# Adafruit_HT16K33_breakout.net
KiCad netlist of a schematic drawn in EAGLE
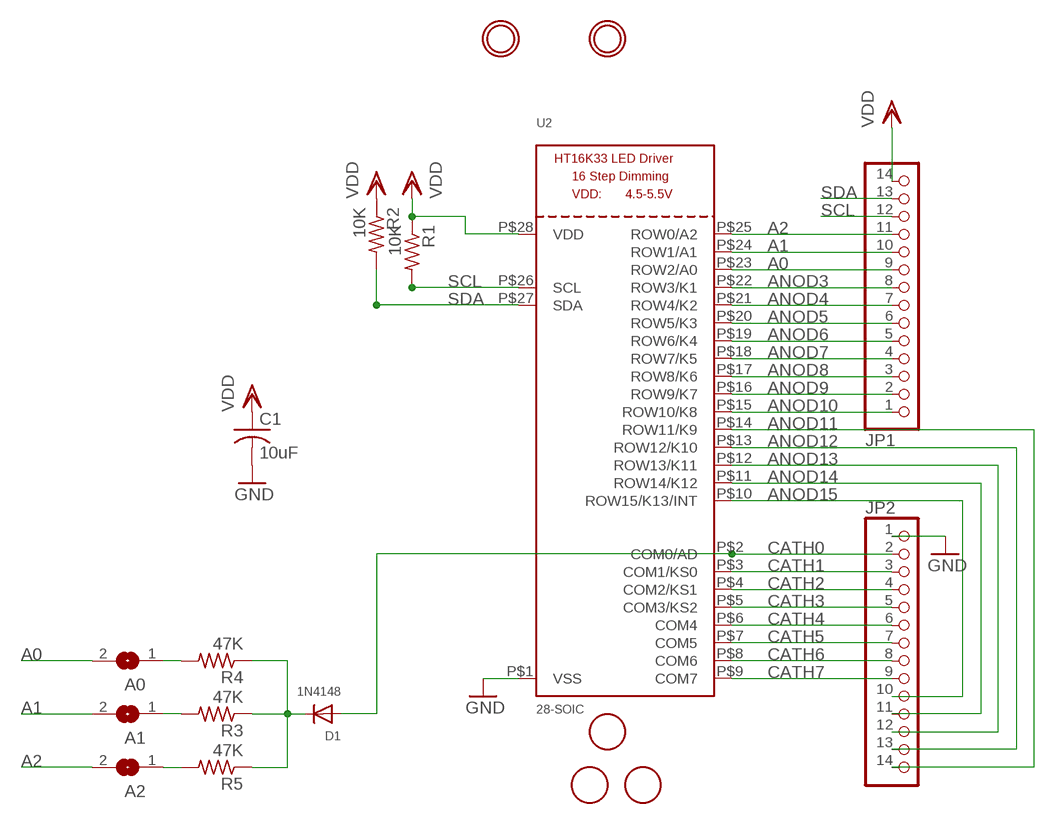
[diagram p0: schematic, sheet 1]

(export (version "E")
  (design (tool "Eeschema 10.0.6"))
  (components
    (comp (ref "A0")
      (value "SOLDERJUMPERREFLOW_NOPASTE")
      (footprint "eagle-import:SOLDERJUMPER_REFLOW_NOPASTE")
      (libsource (lib "eagle-import") (part "SOLDERJUMPERREFLOW_NOPASTE"))
    )
    (comp (ref "A1")
      (value "SOLDERJUMPERREFLOW_NOPASTE")
      (footprint "eagle-import:SOLDERJUMPER_REFLOW_NOPASTE")
      (libsource (lib "eagle-import") (part "SOLDERJUMPERREFLOW_NOPASTE"))
    )
    (comp (ref "A2")
      (value "SOLDERJUMPERREFLOW_NOPASTE")
      (footprint "eagle-import:SOLDERJUMPER_REFLOW_NOPASTE")
      (libsource (lib "eagle-import") (part "SOLDERJUMPERREFLOW_NOPASTE"))
    )
    (comp (ref "C1")
      (value "10uF")
      (footprint "eagle-import:C0805")
      (libsource (lib "eagle-import") (part "C-USC0805"))
    )
    (comp (ref "D1")
      (value "1N4148")
      (footprint "eagle-import:SOD-323F")
      (libsource (lib "eagle-import") (part "DIODESOD-323F"))
    )
    (comp (ref "JP1")
      (value "PINHD-1X14-CB")
      (footprint "eagle-import:1X14-CB")
      (libsource (lib "eagle-import") (part "PINHD-1X14-CB"))
    )
    (comp (ref "JP2")
      (value "PINHD-1X14-CB")
      (footprint "eagle-import:1X14-CB")
      (libsource (lib "eagle-import") (part "PINHD-1X14-CB"))
    )
    (comp (ref "R1")
      (value "10K")
      (footprint "eagle-import:R0805")
      (libsource (lib "eagle-import") (part "R-US_R0805"))
    )
    (comp (ref "R2")
      (value "10K")
      (footprint "eagle-import:R0805")
      (libsource (lib "eagle-import") (part "R-US_R0805"))
    )
    (comp (ref "R3")
      (value "47K")
      (footprint "eagle-import:R0805")
      (libsource (lib "eagle-import") (part "R-US_R0805"))
    )
    (comp (ref "R4")
      (value "47K")
      (footprint "eagle-import:R0805")
      (libsource (lib "eagle-import") (part "R-US_R0805"))
    )
    (comp (ref "R5")
      (value "47K")
      (footprint "eagle-import:R0805")
      (libsource (lib "eagle-import") (part "R-US_R0805"))
    )
    (comp (ref "U$1")
      (value "FIDUCIAL")
      (footprint "eagle-import:FIDUCIAL_1MM")
      (libsource (lib "eagle-import") (part "FIDUCIAL"))
    )
    (comp (ref "U$2")
      (value "FIDUCIAL")
      (footprint "eagle-import:FIDUCIAL_1MM")
      (libsource (lib "eagle-import") (part "FIDUCIAL"))
    )
    (comp (ref "U$4")
      (value "MOUNTINGHOLE2.5")
      (footprint "eagle-import:MOUNTINGHOLE_2.5_PLATED")
      (libsource (lib "eagle-import") (part "MOUNTINGHOLE2.5"))
    )
    (comp (ref "U$5")
      (value "MOUNTINGHOLE2.5")
      (footprint "eagle-import:MOUNTINGHOLE_2.5_PLATED")
      (libsource (lib "eagle-import") (part "MOUNTINGHOLE2.5"))
    )
    (comp (ref "U$6")
      (value "FIDUCIAL")
      (footprint "eagle-import:FIDUCIAL_1MM")
      (libsource (lib "eagle-import") (part "FIDUCIAL"))
    )
    (comp (ref "U2")
      (value "28-SOIC")
      (footprint "eagle-import:SOP28_300MIL")
      (libsource (lib "eagle-import") (part "HT16K33_SOP28"))
    )
  )
  (nets
    (net (code "1") (name "/A0") (class "Default")
      (node (ref "A0") (pin "2") (pinfunction "2_2") (pintype "passive"))
      (node (ref "JP1") (pin "9") (pinfunction "9_9") (pintype "passive"))
      (node (ref "U2") (pin "P$23") (pinfunction "ROW2/A0_P$23") (pintype "bidirectional"))
    )
    (net (code "2") (name "/A1") (class "Default")
      (node (ref "A1") (pin "2") (pinfunction "2_2") (pintype "passive"))
      (node (ref "JP1") (pin "10") (pinfunction "10_10") (pintype "passive"))
      (node (ref "U2") (pin "P$24") (pinfunction "ROW1/A1_P$24") (pintype "bidirectional"))
    )
    (net (code "3") (name "/A2") (class "Default")
      (node (ref "A2") (pin "2") (pinfunction "2_2") (pintype "passive"))
      (node (ref "JP1") (pin "11") (pinfunction "11_11") (pintype "passive"))
      (node (ref "U2") (pin "P$25") (pinfunction "ROW0/A2_P$25") (pintype "bidirectional"))
    )
    (net (code "4") (name "/ANOD3") (class "Default")
      (node (ref "JP1") (pin "8") (pinfunction "8_8") (pintype "passive"))
      (node (ref "U2") (pin "P$22") (pinfunction "ROW3/K1_P$22") (pintype "bidirectional"))
    )
    (net (code "5") (name "/ANOD4") (class "Default")
      (node (ref "JP1") (pin "7") (pinfunction "7_7") (pintype "passive"))
      (node (ref "U2") (pin "P$21") (pinfunction "ROW4/K2_P$21") (pintype "bidirectional"))
    )
    (net (code "6") (name "/ANOD5") (class "Default")
      (node (ref "JP1") (pin "6") (pinfunction "6_6") (pintype "passive"))
      (node (ref "U2") (pin "P$20") (pinfunction "ROW5/K3_P$20") (pintype "bidirectional"))
    )
    (net (code "7") (name "/ANOD6") (class "Default")
      (node (ref "JP1") (pin "5") (pinfunction "5_5") (pintype "passive"))
      (node (ref "U2") (pin "P$19") (pinfunction "ROW6/K4_P$19") (pintype "bidirectional"))
    )
    (net (code "8") (name "/ANOD7") (class "Default")
      (node (ref "JP1") (pin "4") (pinfunction "4_4") (pintype "passive"))
      (node (ref "U2") (pin "P$18") (pinfunction "ROW7/K5_P$18") (pintype "bidirectional"))
    )
    (net (code "9") (name "/ANOD8") (class "Default")
      (node (ref "JP1") (pin "3") (pinfunction "3_3") (pintype "passive"))
      (node (ref "U2") (pin "P$17") (pinfunction "ROW8/K6_P$17") (pintype "bidirectional"))
    )
    (net (code "10") (name "/ANOD9") (class "Default")
      (node (ref "JP1") (pin "2") (pinfunction "2_2") (pintype "passive"))
      (node (ref "U2") (pin "P$16") (pinfunction "ROW9/K7_P$16") (pintype "bidirectional"))
    )
    (net (code "11") (name "/ANOD10") (class "Default")
      (node (ref "JP1") (pin "1") (pinfunction "1_1") (pintype "passive"))
      (node (ref "U2") (pin "P$15") (pinfunction "ROW10/K8_P$15") (pintype "bidirectional"))
    )
    (net (code "12") (name "/ANOD11") (class "Default")
      (node (ref "JP2") (pin "14") (pinfunction "14_14") (pintype "passive"))
      (node (ref "U2") (pin "P$14") (pinfunction "ROW11/K9_P$14") (pintype "bidirectional"))
    )
    (net (code "13") (name "/ANOD12") (class "Default")
      (node (ref "JP2") (pin "13") (pinfunction "13_13") (pintype "passive"))
      (node (ref "U2") (pin "P$13") (pinfunction "ROW12/K10_P$13") (pintype "bidirectional"))
    )
    (net (code "14") (name "/ANOD13") (class "Default")
      (node (ref "JP2") (pin "12") (pinfunction "12_12") (pintype "passive"))
      (node (ref "U2") (pin "P$12") (pinfunction "ROW13/K11_P$12") (pintype "bidirectional"))
    )
    (net (code "15") (name "/ANOD14") (class "Default")
      (node (ref "JP2") (pin "11") (pinfunction "11_11") (pintype "passive"))
      (node (ref "U2") (pin "P$11") (pinfunction "ROW14/K12_P$11") (pintype "bidirectional"))
    )
    (net (code "16") (name "/ANOD15") (class "Default")
      (node (ref "JP2") (pin "10") (pinfunction "10_10") (pintype "passive"))
      (node (ref "U2") (pin "P$10") (pinfunction "ROW15/K13/INT_P$10") (pintype "bidirectional"))
    )
    (net (code "17") (name "/CATH0") (class "Default")
      (node (ref "D1") (pin "A") (pinfunction "A_A") (pintype "passive"))
      (node (ref "JP2") (pin "2") (pinfunction "2_2") (pintype "passive"))
      (node (ref "U2") (pin "P$2") (pinfunction "COM0/AD_P$2") (pintype "bidirectional"))
    )
    (net (code "18") (name "/CATH1") (class "Default")
      (node (ref "JP2") (pin "3") (pinfunction "3_3") (pintype "passive"))
      (node (ref "U2") (pin "P$3") (pinfunction "COM1/KS0_P$3") (pintype "bidirectional"))
    )
    (net (code "19") (name "/CATH2") (class "Default")
      (node (ref "JP2") (pin "4") (pinfunction "4_4") (pintype "passive"))
      (node (ref "U2") (pin "P$4") (pinfunction "COM2/KS1_P$4") (pintype "bidirectional"))
    )
    (net (code "20") (name "/CATH3") (class "Default")
      (node (ref "JP2") (pin "5") (pinfunction "5_5") (pintype "passive"))
      (node (ref "U2") (pin "P$5") (pinfunction "COM3/KS2_P$5") (pintype "bidirectional"))
    )
    (net (code "21") (name "/CATH4") (class "Default")
      (node (ref "JP2") (pin "6") (pinfunction "6_6") (pintype "passive"))
      (node (ref "U2") (pin "P$6") (pinfunction "COM4_P$6") (pintype "bidirectional"))
    )
    (net (code "22") (name "/CATH5") (class "Default")
      (node (ref "JP2") (pin "7") (pinfunction "7_7") (pintype "passive"))
      (node (ref "U2") (pin "P$7") (pinfunction "COM5_P$7") (pintype "bidirectional"))
    )
    (net (code "23") (name "/CATH6") (class "Default")
      (node (ref "JP2") (pin "8") (pinfunction "8_8") (pintype "passive"))
      (node (ref "U2") (pin "P$8") (pinfunction "COM6_P$8") (pintype "bidirectional"))
    )
    (net (code "24") (name "/CATH7") (class "Default")
      (node (ref "JP2") (pin "9") (pinfunction "9_9") (pintype "passive"))
      (node (ref "U2") (pin "P$9") (pinfunction "COM7_P$9") (pintype "bidirectional"))
    )
    (net (code "25") (name "/SCL") (class "Default")
      (node (ref "JP1") (pin "12") (pinfunction "12_12") (pintype "passive"))
      (node (ref "R1") (pin "2") (pinfunction "2_2") (pintype "passive"))
      (node (ref "U2") (pin "P$26") (pinfunction "SCL_P$26") (pintype "bidirectional"))
    )
    (net (code "26") (name "/SDA") (class "Default")
      (node (ref "JP1") (pin "13") (pinfunction "13_13") (pintype "passive"))
      (node (ref "R2") (pin "2") (pinfunction "2_2") (pintype "passive"))
      (node (ref "U2") (pin "P$27") (pinfunction "SDA_P$27") (pintype "bidirectional"))
    )
    (net (code "27") (name "GND") (class "Default")
      (node (ref "C1") (pin "2") (pinfunction "2_2") (pintype "passive"))
      (node (ref "JP2") (pin "1") (pinfunction "1_1") (pintype "passive"))
      (node (ref "U2") (pin "P$1") (pinfunction "VSS_P$1") (pintype "bidirectional"))
    )
    (net (code "28") (name "Net-(A0-Pad1)") (class "Default")
      (node (ref "A0") (pin "1") (pinfunction "1_1") (pintype "passive"))
      (node (ref "R4") (pin "2") (pinfunction "2_2") (pintype "passive"))
    )
    (net (code "29") (name "Net-(A1-Pad1)") (class "Default")
      (node (ref "A1") (pin "1") (pinfunction "1_1") (pintype "passive"))
      (node (ref "R3") (pin "2") (pinfunction "2_2") (pintype "passive"))
    )
    (net (code "30") (name "Net-(A2-Pad1)") (class "Default")
      (node (ref "A2") (pin "1") (pinfunction "1_1") (pintype "passive"))
      (node (ref "R5") (pin "2") (pinfunction "2_2") (pintype "passive"))
    )
    (net (code "31") (name "Net-(D1-PadC)") (class "Default")
      (node (ref "D1") (pin "C") (pinfunction "C_C") (pintype "passive"))
      (node (ref "R3") (pin "1") (pinfunction "1_1") (pintype "passive"))
      (node (ref "R4") (pin "1") (pinfunction "1_1") (pintype "passive"))
      (node (ref "R5") (pin "1") (pinfunction "1_1") (pintype "passive"))
    )
    (net (code "32") (name "VDD") (class "Default")
      (node (ref "C1") (pin "1") (pinfunction "1_1") (pintype "passive"))
      (node (ref "JP1") (pin "14") (pinfunction "14_14") (pintype "passive"))
      (node (ref "R1") (pin "1") (pinfunction "1_1") (pintype "passive"))
      (node (ref "R2") (pin "1") (pinfunction "1_1") (pintype "passive"))
      (node (ref "U2") (pin "P$28") (pinfunction "VDD_P$28") (pintype "bidirectional"))
    )
  )
)
